# test_board.net
KiCad netlist of a schematic drawn in EAGLE
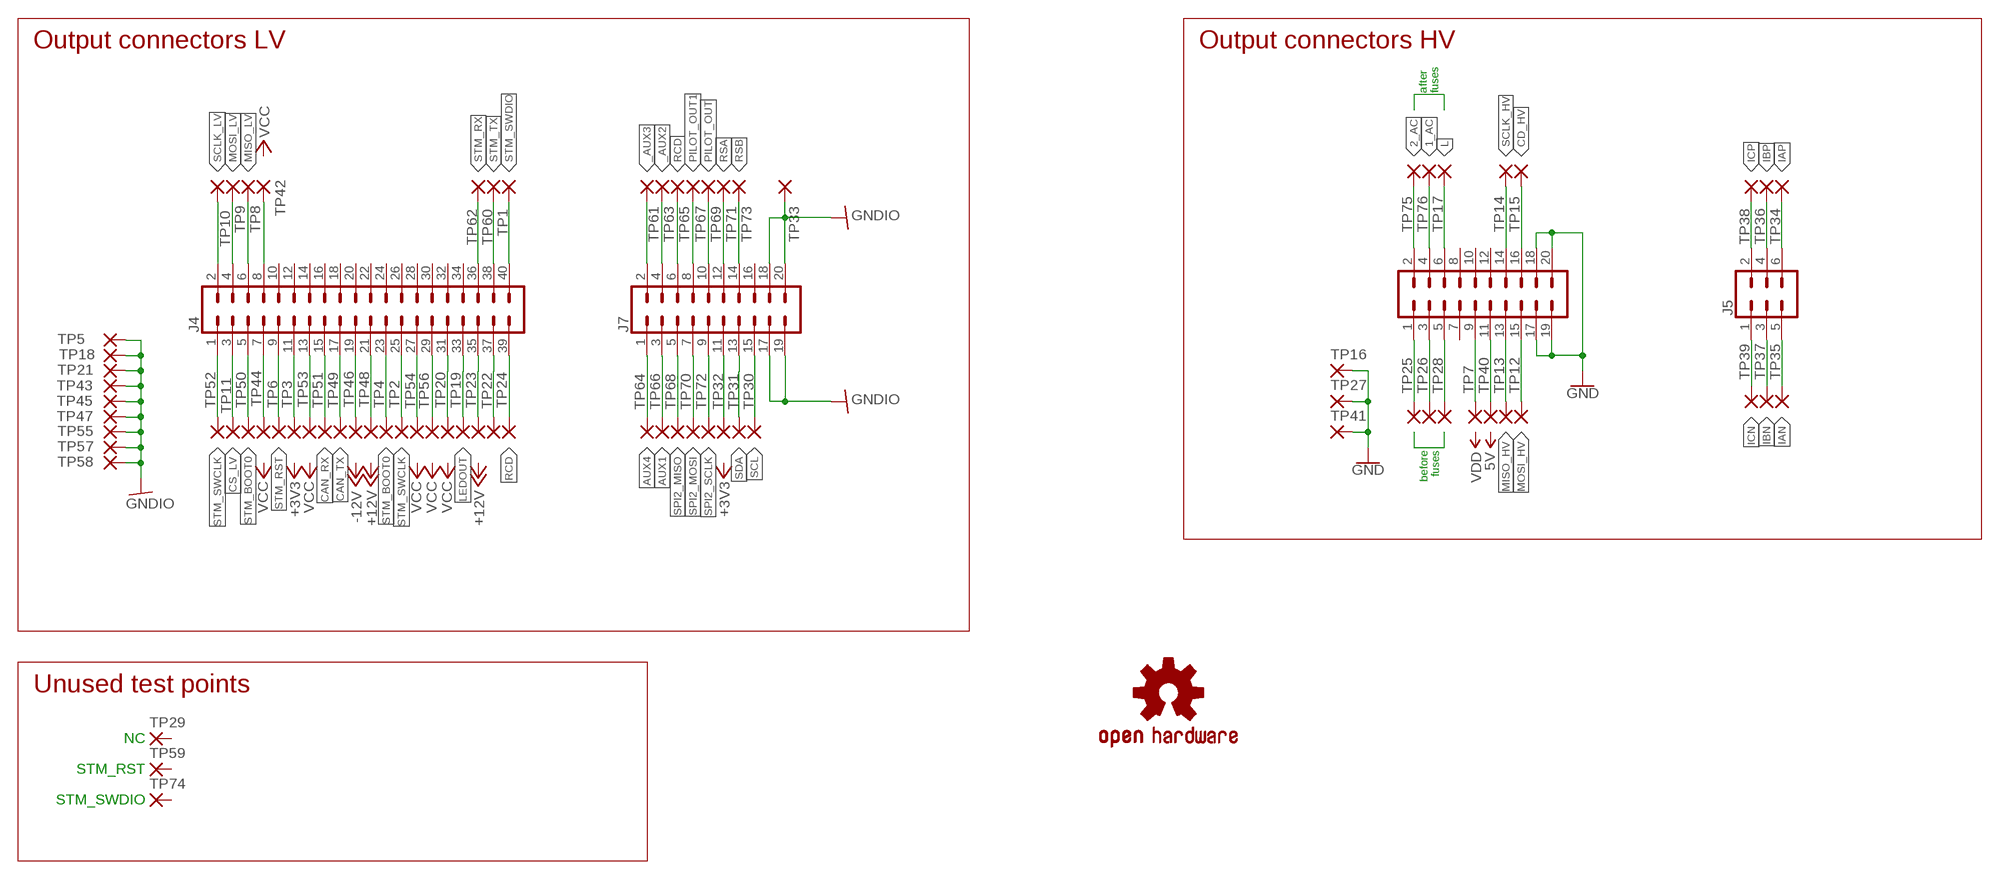
[diagram p0: schematic, sheet 1]

(export (version "E")
  (design (tool "Eeschema 10.0.6"))
  (components
    (comp (ref "J4")
      (value "CONN_20X2SHROUDED")
      (footprint "eagle-import:2X20_SHROUDED")
      (libsource (lib "eagle-import") (part "CONN_20X2SHROUDED"))
    )
    (comp (ref "J5")
      (value "CONN_03X2SHROUD")
      (footprint "eagle-import:2X3-SHROUDED")
      (libsource (lib "eagle-import") (part "CONN_03X2SHROUD"))
    )
    (comp (ref "J7")
      (value "CONN_10X2")
      (footprint "eagle-import:2X10")
      (libsource (lib "eagle-import") (part "CONN_10X2"))
    )
    (comp (ref "J8")
      (value "CONN_10X2")
      (footprint "eagle-import:2X10")
      (libsource (lib "eagle-import") (part "CONN_10X2"))
    )
    (comp (ref "TP1")
      (value "1.35_HOLEROUND")
      (footprint "eagle-import:2,2_1,35_ROUND")
      (libsource (lib "eagle-import") (part "1.35_HOLEROUND"))
    )
    (comp (ref "TP2")
      (value "1.35_HOLEOFFSET")
      (footprint "eagle-import:1,7_1,35_OFFSET")
      (libsource (lib "eagle-import") (part "1.35_HOLEOFFSET"))
    )
    (comp (ref "TP3")
      (value "1.35_HOLEROUND")
      (footprint "eagle-import:2,2_1,35_ROUND")
      (libsource (lib "eagle-import") (part "1.35_HOLEROUND"))
    )
    (comp (ref "TP4")
      (value "1.35_HOLEROUND")
      (footprint "eagle-import:2,2_1,35_ROUND")
      (libsource (lib "eagle-import") (part "1.35_HOLEROUND"))
    )
    (comp (ref "TP5")
      (value "1.35_HOLELONG")
      (footprint "eagle-import:1,7_1,35_LONG")
      (libsource (lib "eagle-import") (part "1.35_HOLELONG"))
    )
    (comp (ref "TP6")
      (value "1.35_HOLEROUND")
      (footprint "eagle-import:2,2_1,35_ROUND")
      (libsource (lib "eagle-import") (part "1.35_HOLEROUND"))
    )
    (comp (ref "TP7")
      (value "1.35_HOLEROUND")
      (footprint "eagle-import:2,2_1,35_ROUND")
      (libsource (lib "eagle-import") (part "1.35_HOLEROUND"))
    )
    (comp (ref "TP8")
      (value "1.35_HOLEOFFSET")
      (footprint "eagle-import:1,7_1,35_OFFSET")
      (libsource (lib "eagle-import") (part "1.35_HOLEOFFSET"))
    )
    (comp (ref "TP9")
      (value "1.35_HOLEOFFSET")
      (footprint "eagle-import:1,7_1,35_OFFSET")
      (libsource (lib "eagle-import") (part "1.35_HOLEOFFSET"))
    )
    (comp (ref "TP10")
      (value "1.35_HOLEOFFSET")
      (footprint "eagle-import:1,7_1,35_OFFSET")
      (libsource (lib "eagle-import") (part "1.35_HOLEOFFSET"))
    )
    (comp (ref "TP11")
      (value "1.35_HOLELONG")
      (footprint "eagle-import:1,7_1,35_LONG")
      (libsource (lib "eagle-import") (part "1.35_HOLELONG"))
    )
    (comp (ref "TP12")
      (value "1.35_HOLEROUND")
      (footprint "eagle-import:2,2_1,35_ROUND")
      (libsource (lib "eagle-import") (part "1.35_HOLEROUND"))
    )
    (comp (ref "TP13")
      (value "1.35_HOLEROUND")
      (footprint "eagle-import:2,2_1,35_ROUND")
      (libsource (lib "eagle-import") (part "1.35_HOLEROUND"))
    )
    (comp (ref "TP14")
      (value "1.35_HOLEOFFSET")
      (footprint "eagle-import:1,7_1,35_OFFSET")
      (libsource (lib "eagle-import") (part "1.35_HOLEOFFSET"))
    )
    (comp (ref "TP15")
      (value "1.35_HOLEOFFSET")
      (footprint "eagle-import:1,7_1,35_OFFSET")
      (libsource (lib "eagle-import") (part "1.35_HOLEOFFSET"))
    )
    (comp (ref "TP16")
      (value "1.35_HOLEROUND")
      (footprint "eagle-import:2,2_1,35_ROUND")
      (libsource (lib "eagle-import") (part "1.35_HOLEROUND"))
    )
    (comp (ref "TP17")
      (value "1.35_HOLEROUND")
      (footprint "eagle-import:2,2_1,35_ROUND")
      (libsource (lib "eagle-import") (part "1.35_HOLEROUND"))
    )
    (comp (ref "TP18")
      (value "1.35_HOLELONG")
      (footprint "eagle-import:1,7_1,35_LONG")
      (libsource (lib "eagle-import") (part "1.35_HOLELONG"))
    )
    (comp (ref "TP19")
      (value "1.35_HOLELONG")
      (footprint "eagle-import:1,7_1,35_LONG")
      (libsource (lib "eagle-import") (part "1.35_HOLELONG"))
    )
    (comp (ref "TP20")
      (value "1.35_HOLELONG")
      (footprint "eagle-import:1,7_1,35_LONG")
      (libsource (lib "eagle-import") (part "1.35_HOLELONG"))
    )
    (comp (ref "TP21")
      (value "1.35_HOLELONG")
      (footprint "eagle-import:1,7_1,35_LONG")
      (libsource (lib "eagle-import") (part "1.35_HOLELONG"))
    )
    (comp (ref "TP22")
      (value "1.35_HOLELONG")
      (footprint "eagle-import:1,7_1,35_LONG")
      (libsource (lib "eagle-import") (part "1.35_HOLELONG"))
    )
    (comp (ref "TP23")
      (value "1.35_HOLELONG")
      (footprint "eagle-import:1,7_1,35_LONG")
      (libsource (lib "eagle-import") (part "1.35_HOLELONG"))
    )
    (comp (ref "TP24")
      (value "1.35_HOLELONG")
      (footprint "eagle-import:1,7_1,35_LONG")
      (libsource (lib "eagle-import") (part "1.35_HOLELONG"))
    )
    (comp (ref "TP25")
      (value "1.35_HOLEROUND")
      (footprint "eagle-import:2,2_1,35_ROUND")
      (libsource (lib "eagle-import") (part "1.35_HOLEROUND"))
    )
    (comp (ref "TP26")
      (value "1.35_HOLEROUND")
      (footprint "eagle-import:2,2_1,35_ROUND")
      (libsource (lib "eagle-import") (part "1.35_HOLEROUND"))
    )
    (comp (ref "TP27")
      (value "1.35_HOLEROUND")
      (footprint "eagle-import:2,2_1,35_ROUND")
      (libsource (lib "eagle-import") (part "1.35_HOLEROUND"))
    )
    (comp (ref "TP28")
      (value "1.35_HOLEROUND")
      (footprint "eagle-import:2,2_1,35_ROUND")
      (libsource (lib "eagle-import") (part "1.35_HOLEROUND"))
    )
    (comp (ref "TP29")
      (value "1.35_HOLELONG")
      (footprint "eagle-import:1,7_1,35_LONG")
      (libsource (lib "eagle-import") (part "1.35_HOLELONG"))
    )
    (comp (ref "TP30")
      (value "1.35_HOLELONG")
      (footprint "eagle-import:1,7_1,35_LONG")
      (libsource (lib "eagle-import") (part "1.35_HOLELONG"))
    )
    (comp (ref "TP31")
      (value "1.35_HOLELONG")
      (footprint "eagle-import:1,7_1,35_LONG")
      (libsource (lib "eagle-import") (part "1.35_HOLELONG"))
    )
    (comp (ref "TP32")
      (value "1.35_HOLELONG")
      (footprint "eagle-import:1,7_1,35_LONG")
      (libsource (lib "eagle-import") (part "1.35_HOLELONG"))
    )
    (comp (ref "TP33")
      (value "1.35_HOLELONG")
      (footprint "eagle-import:1,7_1,35_LONG")
      (libsource (lib "eagle-import") (part "1.35_HOLELONG"))
    )
    (comp (ref "TP34")
      (value "1.35_HOLELONG")
      (footprint "eagle-import:1,7_1,35_LONG")
      (libsource (lib "eagle-import") (part "1.35_HOLELONG"))
    )
    (comp (ref "TP35")
      (value "1.35_HOLELONG")
      (footprint "eagle-import:1,7_1,35_LONG")
      (libsource (lib "eagle-import") (part "1.35_HOLELONG"))
    )
    (comp (ref "TP36")
      (value "1.35_HOLELONG")
      (footprint "eagle-import:1,7_1,35_LONG")
      (libsource (lib "eagle-import") (part "1.35_HOLELONG"))
    )
    (comp (ref "TP37")
      (value "1.35_HOLELONG")
      (footprint "eagle-import:1,7_1,35_LONG")
      (libsource (lib "eagle-import") (part "1.35_HOLELONG"))
    )
    (comp (ref "TP38")
      (value "1.35_HOLELONG")
      (footprint "eagle-import:1,7_1,35_LONG")
      (libsource (lib "eagle-import") (part "1.35_HOLELONG"))
    )
    (comp (ref "TP39")
      (value "1.35_HOLELONG")
      (footprint "eagle-import:1,7_1,35_LONG")
      (libsource (lib "eagle-import") (part "1.35_HOLELONG"))
    )
    (comp (ref "TP40")
      (value "1.35_HOLELONG")
      (footprint "eagle-import:1,7_1,35_LONG")
      (libsource (lib "eagle-import") (part "1.35_HOLELONG"))
    )
    (comp (ref "TP41")
      (value "1.35_HOLELONG")
      (footprint "eagle-import:1,7_1,35_LONG")
      (libsource (lib "eagle-import") (part "1.35_HOLELONG"))
    )
    (comp (ref "TP42")
      (value "1.35_HOLELONG")
      (footprint "eagle-import:1,7_1,35_LONG")
      (libsource (lib "eagle-import") (part "1.35_HOLELONG"))
    )
    (comp (ref "TP43")
      (value "1.35_HOLELONG")
      (footprint "eagle-import:1,7_1,35_LONG")
      (libsource (lib "eagle-import") (part "1.35_HOLELONG"))
    )
    (comp (ref "TP44")
      (value "1.35_HOLELONG")
      (footprint "eagle-import:1,7_1,35_LONG")
      (libsource (lib "eagle-import") (part "1.35_HOLELONG"))
    )
    (comp (ref "TP45")
      (value "1.35_HOLELONG")
      (footprint "eagle-import:1,7_1,35_LONG")
      (libsource (lib "eagle-import") (part "1.35_HOLELONG"))
    )
    (comp (ref "TP46")
      (value "1.35_HOLELONG")
      (footprint "eagle-import:1,7_1,35_LONG")
      (libsource (lib "eagle-import") (part "1.35_HOLELONG"))
    )
    (comp (ref "TP47")
      (value "1.35_HOLELONG")
      (footprint "eagle-import:1,7_1,35_LONG")
      (libsource (lib "eagle-import") (part "1.35_HOLELONG"))
    )
    (comp (ref "TP48")
      (value "1.35_HOLELONG")
      (footprint "eagle-import:1,7_1,35_LONG")
      (libsource (lib "eagle-import") (part "1.35_HOLELONG"))
    )
    (comp (ref "TP49")
      (value "1.35_HOLEROUND")
      (footprint "eagle-import:2,2_1,35_ROUND")
      (libsource (lib "eagle-import") (part "1.35_HOLEROUND"))
    )
    (comp (ref "TP50")
      (value "1.35_HOLEROUND")
      (footprint "eagle-import:2,2_1,35_ROUND")
      (libsource (lib "eagle-import") (part "1.35_HOLEROUND"))
    )
    (comp (ref "TP51")
      (value "1.35_HOLEROUND")
      (footprint "eagle-import:2,2_1,35_ROUND")
      (libsource (lib "eagle-import") (part "1.35_HOLEROUND"))
    )
    (comp (ref "TP52")
      (value "1.35_HOLEROUND")
      (footprint "eagle-import:2,2_1,35_ROUND")
      (libsource (lib "eagle-import") (part "1.35_HOLEROUND"))
    )
    (comp (ref "TP53")
      (value "1.35_HOLEROUND")
      (footprint "eagle-import:2,2_1,35_ROUND")
      (libsource (lib "eagle-import") (part "1.35_HOLEROUND"))
    )
    (comp (ref "TP54")
      (value "1.35_HOLEROUND")
      (footprint "eagle-import:2,2_1,35_ROUND")
      (libsource (lib "eagle-import") (part "1.35_HOLEROUND"))
    )
    (comp (ref "TP55")
      (value "1.35_HOLEROUND")
      (footprint "eagle-import:2,2_1,35_ROUND")
      (libsource (lib "eagle-import") (part "1.35_HOLEROUND"))
    )
    (comp (ref "TP56")
      (value "1.35_HOLEROUND")
      (footprint "eagle-import:2,2_1,35_ROUND")
      (libsource (lib "eagle-import") (part "1.35_HOLEROUND"))
    )
    (comp (ref "TP57")
      (value "1.35_HOLEROUND")
      (footprint "eagle-import:2,2_1,35_ROUND")
      (libsource (lib "eagle-import") (part "1.35_HOLEROUND"))
    )
    (comp (ref "TP58")
      (value "1.35_HOLEROUND")
      (footprint "eagle-import:2,2_1,35_ROUND")
      (libsource (lib "eagle-import") (part "1.35_HOLEROUND"))
    )
    (comp (ref "TP59")
      (value "1.35_HOLEROUND")
      (footprint "eagle-import:2,2_1,35_ROUND")
      (libsource (lib "eagle-import") (part "1.35_HOLEROUND"))
    )
    (comp (ref "TP60")
      (value "1.35_HOLEROUND")
      (footprint "eagle-import:2,2_1,35_ROUND")
      (libsource (lib "eagle-import") (part "1.35_HOLEROUND"))
    )
    (comp (ref "TP61")
      (value "1.35_HOLEROUND")
      (footprint "eagle-import:2,2_1,35_ROUND")
      (libsource (lib "eagle-import") (part "1.35_HOLEROUND"))
    )
    (comp (ref "TP62")
      (value "1.35_HOLEROUND")
      (footprint "eagle-import:2,2_1,35_ROUND")
      (libsource (lib "eagle-import") (part "1.35_HOLEROUND"))
    )
    (comp (ref "TP63")
      (value "1.35_HOLEROUND")
      (footprint "eagle-import:2,2_1,35_ROUND")
      (libsource (lib "eagle-import") (part "1.35_HOLEROUND"))
    )
    (comp (ref "TP64")
      (value "1.35_HOLEROUND")
      (footprint "eagle-import:2,2_1,35_ROUND")
      (libsource (lib "eagle-import") (part "1.35_HOLEROUND"))
    )
    (comp (ref "TP65")
      (value "1.35_HOLEROUND")
      (footprint "eagle-import:2,2_1,35_ROUND")
      (libsource (lib "eagle-import") (part "1.35_HOLEROUND"))
    )
    (comp (ref "TP66")
      (value "1.35_HOLEROUND")
      (footprint "eagle-import:2,2_1,35_ROUND")
      (libsource (lib "eagle-import") (part "1.35_HOLEROUND"))
    )
    (comp (ref "TP67")
      (value "1.35_HOLEROUND")
      (footprint "eagle-import:2,2_1,35_ROUND")
      (libsource (lib "eagle-import") (part "1.35_HOLEROUND"))
    )
    (comp (ref "TP68")
      (value "1.35_HOLEROUND")
      (footprint "eagle-import:2,2_1,35_ROUND")
      (libsource (lib "eagle-import") (part "1.35_HOLEROUND"))
    )
    (comp (ref "TP69")
      (value "1.35_HOLEROUND")
      (footprint "eagle-import:2,2_1,35_ROUND")
      (libsource (lib "eagle-import") (part "1.35_HOLEROUND"))
    )
    (comp (ref "TP70")
      (value "1.35_HOLEROUND")
      (footprint "eagle-import:2,2_1,35_ROUND")
      (libsource (lib "eagle-import") (part "1.35_HOLEROUND"))
    )
    (comp (ref "TP71")
      (value "1.35_HOLEROUND")
      (footprint "eagle-import:2,2_1,35_ROUND")
      (libsource (lib "eagle-import") (part "1.35_HOLEROUND"))
    )
    (comp (ref "TP72")
      (value "1.35_HOLEROUND")
      (footprint "eagle-import:2,2_1,35_ROUND")
      (libsource (lib "eagle-import") (part "1.35_HOLEROUND"))
    )
    (comp (ref "TP73")
      (value "1.35_HOLEROUND")
      (footprint "eagle-import:2,2_1,35_ROUND")
      (libsource (lib "eagle-import") (part "1.35_HOLEROUND"))
    )
    (comp (ref "TP74")
      (value "1.35_HOLEROUND")
      (footprint "eagle-import:2,2_1,35_ROUND")
      (libsource (lib "eagle-import") (part "1.35_HOLEROUND"))
    )
    (comp (ref "TP75")
      (value "1.35_HOLEROUND")
      (footprint "eagle-import:2,2_1,35_ROUND")
      (libsource (lib "eagle-import") (part "1.35_HOLEROUND"))
    )
    (comp (ref "TP76")
      (value "1.35_HOLEROUND")
      (footprint "eagle-import:2,2_1,35_ROUND")
      (libsource (lib "eagle-import") (part "1.35_HOLEROUND"))
    )
    (comp (ref "U$1")
      (value "OSHW-LOGOL")
      (footprint "eagle-import:OSHW-LOGO-L")
      (libsource (lib "eagle-import") (part "OSHW-LOGOL"))
    )
  )
  (nets
    (net (code "4") (name "1_AC") (class "Default")
      (node (ref "J8") (pin "4") (pinfunction "4_4") (pintype "passive"))
      (node (ref "TP76") (pin "1") (pinfunction "P_1") (pintype "passive"))
    )
    (net (code "5") (name "2_AC") (class "Default")
      (node (ref "J8") (pin "2") (pinfunction "2_2") (pintype "passive"))
      (node (ref "TP75") (pin "1") (pinfunction "P_1") (pintype "passive"))
    )
    (net (code "7") (name "AUX1") (class "Default")
      (node (ref "J7") (pin "3") (pinfunction "3_3") (pintype "passive"))
      (node (ref "TP66") (pin "1") (pinfunction "P_1") (pintype "passive"))
    )
    (net (code "8") (name "AUX4") (class "Default")
      (node (ref "J7") (pin "1") (pinfunction "1_1") (pintype "passive"))
      (node (ref "TP64") (pin "1") (pinfunction "P_1") (pintype "passive"))
    )
    (net (code "9") (name "CAN_RX") (class "Default")
      (node (ref "J4") (pin "15") (pinfunction "15_15") (pintype "passive"))
      (node (ref "TP51") (pin "1") (pinfunction "P_1") (pintype "passive"))
    )
    (net (code "10") (name "CAN_TX") (class "Default")
      (node (ref "J4") (pin "17") (pinfunction "17_17") (pintype "passive"))
      (node (ref "TP49") (pin "1") (pinfunction "P_1") (pintype "passive"))
    )
    (net (code "11") (name "CD_HV") (class "Default")
      (node (ref "J8") (pin "16") (pinfunction "16_16") (pintype "passive"))
      (node (ref "TP15") (pin "1") (pinfunction "P_1") (pintype "passive"))
    )
    (net (code "12") (name "CS_LV") (class "Default")
      (node (ref "J4") (pin "3") (pinfunction "3_3") (pintype "passive"))
      (node (ref "TP11") (pin "1") (pinfunction "P_1") (pintype "passive"))
    )
    (net (code "13") (name "GND") (class "Default")
      (node (ref "J8") (pin "17") (pinfunction "17_17") (pintype "passive"))
      (node (ref "J8") (pin "18") (pinfunction "18_18") (pintype "passive"))
      (node (ref "J8") (pin "19") (pinfunction "19_19") (pintype "passive"))
      (node (ref "J8") (pin "20") (pinfunction "20_20") (pintype "passive"))
      (node (ref "TP16") (pin "1") (pinfunction "P_1") (pintype "passive"))
      (node (ref "TP27") (pin "1") (pinfunction "P_1") (pintype "passive"))
      (node (ref "TP41") (pin "1") (pinfunction "P_1") (pintype "passive"))
    )
    (net (code "14") (name "GNDIO") (class "Default")
      (node (ref "J7") (pin "17") (pinfunction "17_17") (pintype "passive"))
      (node (ref "J7") (pin "18") (pinfunction "18_18") (pintype "passive"))
      (node (ref "J7") (pin "19") (pinfunction "19_19") (pintype "passive"))
      (node (ref "J7") (pin "20") (pinfunction "20_20") (pintype "passive"))
      (node (ref "TP18") (pin "1") (pinfunction "P_1") (pintype "passive"))
      (node (ref "TP21") (pin "1") (pinfunction "P_1") (pintype "passive"))
      (node (ref "TP33") (pin "1") (pinfunction "P_1") (pintype "passive"))
      (node (ref "TP43") (pin "1") (pinfunction "P_1") (pintype "passive"))
      (node (ref "TP45") (pin "1") (pinfunction "P_1") (pintype "passive"))
      (node (ref "TP47") (pin "1") (pinfunction "P_1") (pintype "passive"))
      (node (ref "TP5") (pin "1") (pinfunction "P_1") (pintype "passive"))
      (node (ref "TP55") (pin "1") (pinfunction "P_1") (pintype "passive"))
      (node (ref "TP57") (pin "1") (pinfunction "P_1") (pintype "passive"))
      (node (ref "TP58") (pin "1") (pinfunction "P_1") (pintype "passive"))
    )
    (net (code "15") (name "IAN") (class "Default")
      (node (ref "J5") (pin "5") (pinfunction "5_5") (pintype "bidirectional"))
      (node (ref "TP35") (pin "1") (pinfunction "P_1") (pintype "passive"))
    )
    (net (code "16") (name "IAP") (class "Default")
      (node (ref "J5") (pin "6") (pinfunction "6_6") (pintype "bidirectional"))
      (node (ref "TP34") (pin "1") (pinfunction "P_1") (pintype "passive"))
    )
    (net (code "17") (name "IBN") (class "Default")
      (node (ref "J5") (pin "3") (pinfunction "3_3") (pintype "bidirectional"))
      (node (ref "TP37") (pin "1") (pinfunction "P_1") (pintype "passive"))
    )
    (net (code "18") (name "IBP") (class "Default")
      (node (ref "J5") (pin "4") (pinfunction "4_4") (pintype "bidirectional"))
      (node (ref "TP36") (pin "1") (pinfunction "P_1") (pintype "passive"))
    )
    (net (code "19") (name "ICN") (class "Default")
      (node (ref "J5") (pin "1") (pinfunction "1_1") (pintype "bidirectional"))
      (node (ref "TP39") (pin "1") (pinfunction "P_1") (pintype "passive"))
    )
    (net (code "20") (name "ICP") (class "Default")
      (node (ref "J5") (pin "2") (pinfunction "2_2") (pintype "bidirectional"))
      (node (ref "TP38") (pin "1") (pinfunction "P_1") (pintype "passive"))
    )
    (net (code "21") (name "L") (class "Default")
      (node (ref "J8") (pin "6") (pinfunction "6_6") (pintype "passive"))
      (node (ref "TP17") (pin "1") (pinfunction "P_1") (pintype "passive"))
    )
    (net (code "22") (name "LEDOUT") (class "Default")
      (node (ref "J4") (pin "33") (pinfunction "33_33") (pintype "passive"))
      (node (ref "TP19") (pin "1") (pinfunction "P_1") (pintype "passive"))
    )
    (net (code "23") (name "MISO_HV") (class "Default")
      (node (ref "J8") (pin "13") (pinfunction "13_13") (pintype "passive"))
      (node (ref "TP13") (pin "1") (pinfunction "P_1") (pintype "passive"))
    )
    (net (code "24") (name "MISO_LV") (class "Default")
      (node (ref "J4") (pin "6") (pinfunction "6_6") (pintype "passive"))
      (node (ref "TP8") (pin "1") (pinfunction "P_1") (pintype "passive"))
    )
    (net (code "25") (name "MOSI_HV") (class "Default")
      (node (ref "J8") (pin "15") (pinfunction "15_15") (pintype "passive"))
      (node (ref "TP12") (pin "1") (pinfunction "P_1") (pintype "passive"))
    )
    (net (code "26") (name "MOSI_LV") (class "Default")
      (node (ref "J4") (pin "4") (pinfunction "4_4") (pintype "passive"))
      (node (ref "TP9") (pin "1") (pinfunction "P_1") (pintype "passive"))
    )
    (net (code "27") (name "Net-(TP3-P)") (class "Default")
      (node (ref "J4") (pin "11") (pinfunction "11_11") (pintype "passive"))
      (node (ref "TP3") (pin "1") (pinfunction "P_1") (pintype "passive"))
    )
    (net (code "28") (name "Net-(TP7-P)") (class "Default")
      (node (ref "J8") (pin "9") (pinfunction "9_9") (pintype "passive"))
      (node (ref "TP7") (pin "1") (pinfunction "P_1") (pintype "passive"))
    )
    (net (code "29") (name "Net-(TP20-P)") (class "Default")
      (node (ref "J4") (pin "31") (pinfunction "31_31") (pintype "passive"))
      (node (ref "TP20") (pin "1") (pinfunction "P_1") (pintype "passive"))
    )
    (net (code "30") (name "Net-(TP22-P)") (class "Default")
      (node (ref "J4") (pin "37") (pinfunction "37_37") (pintype "passive"))
      (node (ref "TP22") (pin "1") (pinfunction "P_1") (pintype "passive"))
    )
    (net (code "31") (name "Net-(TP23-P)") (class "Default")
      (node (ref "J4") (pin "35") (pinfunction "35_35") (pintype "passive"))
      (node (ref "TP23") (pin "1") (pinfunction "P_1") (pintype "passive"))
    )
    (net (code "32") (name "Net-(TP25-P)") (class "Default")
      (node (ref "J8") (pin "1") (pinfunction "1_1") (pintype "passive"))
      (node (ref "TP25") (pin "1") (pinfunction "P_1") (pintype "passive"))
    )
    (net (code "33") (name "Net-(TP26-P)") (class "Default")
      (node (ref "J8") (pin "3") (pinfunction "3_3") (pintype "passive"))
      (node (ref "TP26") (pin "1") (pinfunction "P_1") (pintype "passive"))
    )
    (net (code "34") (name "Net-(TP28-P)") (class "Default")
      (node (ref "J8") (pin "5") (pinfunction "5_5") (pintype "passive"))
      (node (ref "TP28") (pin "1") (pinfunction "P_1") (pintype "passive"))
    )
    (net (code "35") (name "Net-(TP32-P)") (class "Default")
      (node (ref "J7") (pin "11") (pinfunction "11_11") (pintype "passive"))
      (node (ref "TP32") (pin "1") (pinfunction "P_1") (pintype "passive"))
    )
    (net (code "36") (name "Net-(TP40-P)") (class "Default")
      (node (ref "J8") (pin "11") (pinfunction "11_11") (pintype "passive"))
      (node (ref "TP40") (pin "1") (pinfunction "P_1") (pintype "passive"))
    )
    (net (code "37") (name "Net-(TP42-P)") (class "Default")
      (node (ref "J4") (pin "8") (pinfunction "8_8") (pintype "passive"))
      (node (ref "TP42") (pin "1") (pinfunction "P_1") (pintype "passive"))
    )
    (net (code "38") (name "Net-(TP44-P)") (class "Default")
      (node (ref "J4") (pin "7") (pinfunction "7_7") (pintype "passive"))
      (node (ref "TP44") (pin "1") (pinfunction "P_1") (pintype "passive"))
    )
    (net (code "39") (name "Net-(TP46-P)") (class "Default")
      (node (ref "J4") (pin "19") (pinfunction "19_19") (pintype "passive"))
      (node (ref "TP46") (pin "1") (pinfunction "P_1") (pintype "passive"))
    )
    (net (code "40") (name "Net-(TP48-P)") (class "Default")
      (node (ref "J4") (pin "21") (pinfunction "21_21") (pintype "passive"))
      (node (ref "TP48") (pin "1") (pinfunction "P_1") (pintype "passive"))
    )
    (net (code "41") (name "Net-(TP53-P)") (class "Default")
      (node (ref "J4") (pin "13") (pinfunction "13_13") (pintype "passive"))
      (node (ref "TP53") (pin "1") (pinfunction "P_1") (pintype "passive"))
    )
    (net (code "42") (name "Net-(TP54-P)") (class "Default")
      (node (ref "J4") (pin "27") (pinfunction "27_27") (pintype "passive"))
      (node (ref "TP54") (pin "1") (pinfunction "P_1") (pintype "passive"))
    )
    (net (code "43") (name "Net-(TP56-P)") (class "Default")
      (node (ref "J4") (pin "29") (pinfunction "29_29") (pintype "passive"))
      (node (ref "TP56") (pin "1") (pinfunction "P_1") (pintype "passive"))
    )
    (net (code "44") (name "PILOT_OUT") (class "Default")
      (node (ref "J7") (pin "10") (pinfunction "10_10") (pintype "passive"))
      (node (ref "TP69") (pin "1") (pinfunction "P_1") (pintype "passive"))
    )
    (net (code "45") (name "PILOT_OUT1") (class "Default")
      (node (ref "J7") (pin "8") (pinfunction "8_8") (pintype "passive"))
      (node (ref "TP67") (pin "1") (pinfunction "P_1") (pintype "passive"))
    )
    (net (code "46") (name "RCD") (class "Default")
      (node (ref "J4") (pin "39") (pinfunction "39_39") (pintype "passive"))
      (node (ref "J7") (pin "6") (pinfunction "6_6") (pintype "passive"))
      (node (ref "TP24") (pin "1") (pinfunction "P_1") (pintype "passive"))
      (node (ref "TP65") (pin "1") (pinfunction "P_1") (pintype "passive"))
    )
    (net (code "47") (name "RSA") (class "Default")
      (node (ref "J7") (pin "12") (pinfunction "12_12") (pintype "passive"))
      (node (ref "TP71") (pin "1") (pinfunction "P_1") (pintype "passive"))
    )
    (net (code "48") (name "RSB") (class "Default")
      (node (ref "J7") (pin "14") (pinfunction "14_14") (pintype "passive"))
      (node (ref "TP73") (pin "1") (pinfunction "P_1") (pintype "passive"))
    )
    (net (code "49") (name "SCL") (class "Default")
      (node (ref "J7") (pin "15") (pinfunction "15_15") (pintype "passive"))
      (node (ref "TP30") (pin "1") (pinfunction "P_1") (pintype "passive"))
    )
    (net (code "50") (name "SCLK_HV") (class "Default")
      (node (ref "J8") (pin "14") (pinfunction "14_14") (pintype "passive"))
      (node (ref "TP14") (pin "1") (pinfunction "P_1") (pintype "passive"))
    )
    (net (code "51") (name "SCLK_LV") (class "Default")
      (node (ref "J4") (pin "2") (pinfunction "2_2") (pintype "passive"))
      (node (ref "TP10") (pin "1") (pinfunction "P_1") (pintype "passive"))
    )
    (net (code "52") (name "SDA") (class "Default")
      (node (ref "J7") (pin "13") (pinfunction "13_13") (pintype "passive"))
      (node (ref "TP31") (pin "1") (pinfunction "P_1") (pintype "passive"))
    )
    (net (code "53") (name "SPI2_MISO") (class "Default")
      (node (ref "J7") (pin "5") (pinfunction "5_5") (pintype "passive"))
      (node (ref "TP68") (pin "1") (pinfunction "P_1") (pintype "passive"))
    )
    (net (code "54") (name "SPI2_MOSI") (class "Default")
      (node (ref "J7") (pin "7") (pinfunction "7_7") (pintype "passive"))
      (node (ref "TP70") (pin "1") (pinfunction "P_1") (pintype "passive"))
    )
    (net (code "55") (name "SPI2_SCLK") (class "Default")
      (node (ref "J7") (pin "9") (pinfunction "9_9") (pintype "passive"))
      (node (ref "TP72") (pin "1") (pinfunction "P_1") (pintype "passive"))
    )
    (net (code "56") (name "STM_BOOT0") (class "Default")
      (node (ref "J4") (pin "23") (pinfunction "23_23") (pintype "passive"))
      (node (ref "J4") (pin "5") (pinfunction "5_5") (pintype "passive"))
      (node (ref "TP4") (pin "1") (pinfunction "P_1") (pintype "passive"))
      (node (ref "TP50") (pin "1") (pinfunction "P_1") (pintype "passive"))
    )
    (net (code "57") (name "STM_RST") (class "Default")
      (node (ref "J4") (pin "9") (pinfunction "9_9") (pintype "passive"))
      (node (ref "TP6") (pin "1") (pinfunction "P_1") (pintype "passive"))
    )
    (net (code "58") (name "STM_RX") (class "Default")
      (node (ref "J4") (pin "36") (pinfunction "36_36") (pintype "passive"))
      (node (ref "TP62") (pin "1") (pinfunction "P_1") (pintype "passive"))
    )
    (net (code "59") (name "STM_SWCLK") (class "Default")
      (node (ref "J4") (pin "1") (pinfunction "1_1") (pintype "passive"))
      (node (ref "J4") (pin "25") (pinfunction "25_25") (pintype "passive"))
      (node (ref "TP2") (pin "1") (pinfunction "P_1") (pintype "passive"))
      (node (ref "TP52") (pin "1") (pinfunction "P_1") (pintype "passive"))
    )
    (net (code "60") (name "STM_SWDIO") (class "Default")
      (node (ref "J4") (pin "40") (pinfunction "40_40") (pintype "passive"))
      (node (ref "TP1") (pin "1") (pinfunction "P_1") (pintype "passive"))
    )
    (net (code "61") (name "STM_TX") (class "Default")
      (node (ref "J4") (pin "38") (pinfunction "38_38") (pintype "passive"))
      (node (ref "TP60") (pin "1") (pinfunction "P_1") (pintype "passive"))
    )
    (net (code "64") (name "_AUX2") (class "Default")
      (node (ref "J7") (pin "4") (pinfunction "4_4") (pintype "passive"))
      (node (ref "TP63") (pin "1") (pinfunction "P_1") (pintype "passive"))
    )
    (net (code "65") (name "_AUX3") (class "Default")
      (node (ref "J7") (pin "2") (pinfunction "2_2") (pintype "passive"))
      (node (ref "TP61") (pin "1") (pinfunction "P_1") (pintype "passive"))
    )
    (net (code "66") (name "unconnected-(J4-Pad10)") (class "Default")
      (node (ref "J4") (pin "10") (pinfunction "10_10") (pintype "passive"))
    )
    (net (code "67") (name "unconnected-(J4-Pad12)") (class "Default")
      (node (ref "J4") (pin "12") (pinfunction "12_12") (pintype "passive"))
    )
    (net (code "68") (name "unconnected-(J4-Pad14)") (class "Default")
      (node (ref "J4") (pin "14") (pinfunction "14_14") (pintype "passive"))
    )
    (net (code "69") (name "unconnected-(J4-Pad16)") (class "Default")
      (node (ref "J4") (pin "16") (pinfunction "16_16") (pintype "passive"))
    )
    (net (code "70") (name "unconnected-(J4-Pad18)") (class "Default")
      (node (ref "J4") (pin "18") (pinfunction "18_18") (pintype "passive"))
    )
    (net (code "71") (name "unconnected-(J4-Pad20)") (class "Default")
      (node (ref "J4") (pin "20") (pinfunction "20_20") (pintype "passive"))
    )
    (net (code "72") (name "unconnected-(J4-Pad22)") (class "Default")
      (node (ref "J4") (pin "22") (pinfunction "22_22") (pintype "passive"))
    )
    (net (code "73") (name "unconnected-(J4-Pad24)") (class "Default")
      (node (ref "J4") (pin "24") (pinfunction "24_24") (pintype "passive"))
    )
    (net (code "74") (name "unconnected-(J4-Pad26)") (class "Default")
      (node (ref "J4") (pin "26") (pinfunction "26_26") (pintype "passive"))
    )
    (net (code "75") (name "unconnected-(J4-Pad28)") (class "Default")
      (node (ref "J4") (pin "28") (pinfunction "28_28") (pintype "passive"))
    )
    (net (code "76") (name "unconnected-(J4-Pad30)") (class "Default")
      (node (ref "J4") (pin "30") (pinfunction "30_30") (pintype "passive"))
    )
    (net (code "77") (name "unconnected-(J4-Pad32)") (class "Default")
      (node (ref "J4") (pin "32") (pinfunction "32_32") (pintype "passive"))
    )
    (net (code "78") (name "unconnected-(J4-Pad34)") (class "Default")
      (node (ref "J4") (pin "34") (pinfunction "34_34") (pintype "passive"))
    )
    (net (code "79") (name "unconnected-(J7-Pad16)") (class "Default")
      (node (ref "J7") (pin "16") (pinfunction "16_16") (pintype "passive"))
    )
    (net (code "80") (name "unconnected-(J8-Pad7)") (class "Default")
      (node (ref "J8") (pin "7") (pinfunction "7_7") (pintype "passive"))
    )
    (net (code "81") (name "unconnected-(J8-Pad8)") (class "Default")
      (node (ref "J8") (pin "8") (pinfunction "8_8") (pintype "passive"))
    )
    (net (code "82") (name "unconnected-(J8-Pad10)") (class "Default")
      (node (ref "J8") (pin "10") (pinfunction "10_10") (pintype "passive"))
    )
    (net (code "83") (name "unconnected-(J8-Pad12)") (class "Default")
      (node (ref "J8") (pin "12") (pinfunction "12_12") (pintype "passive"))
    )
    (net (code "84") (name "unconnected-(TP29-P-Pad1)") (class "Default")
      (node (ref "TP29") (pin "1") (pinfunction "P_1") (pintype "passive"))
    )
    (net (code "85") (name "unconnected-(TP59-P-Pad1)") (class "Default")
      (node (ref "TP59") (pin "1") (pinfunction "P_1") (pintype "passive"))
    )
    (net (code "86") (name "unconnected-(TP74-P-Pad1)") (class "Default")
      (node (ref "TP74") (pin "1") (pinfunction "P_1") (pintype "passive"))
    )
  )
)
